# HP85disk.net
KiCad netlist of a schematic drawn in EAGLE
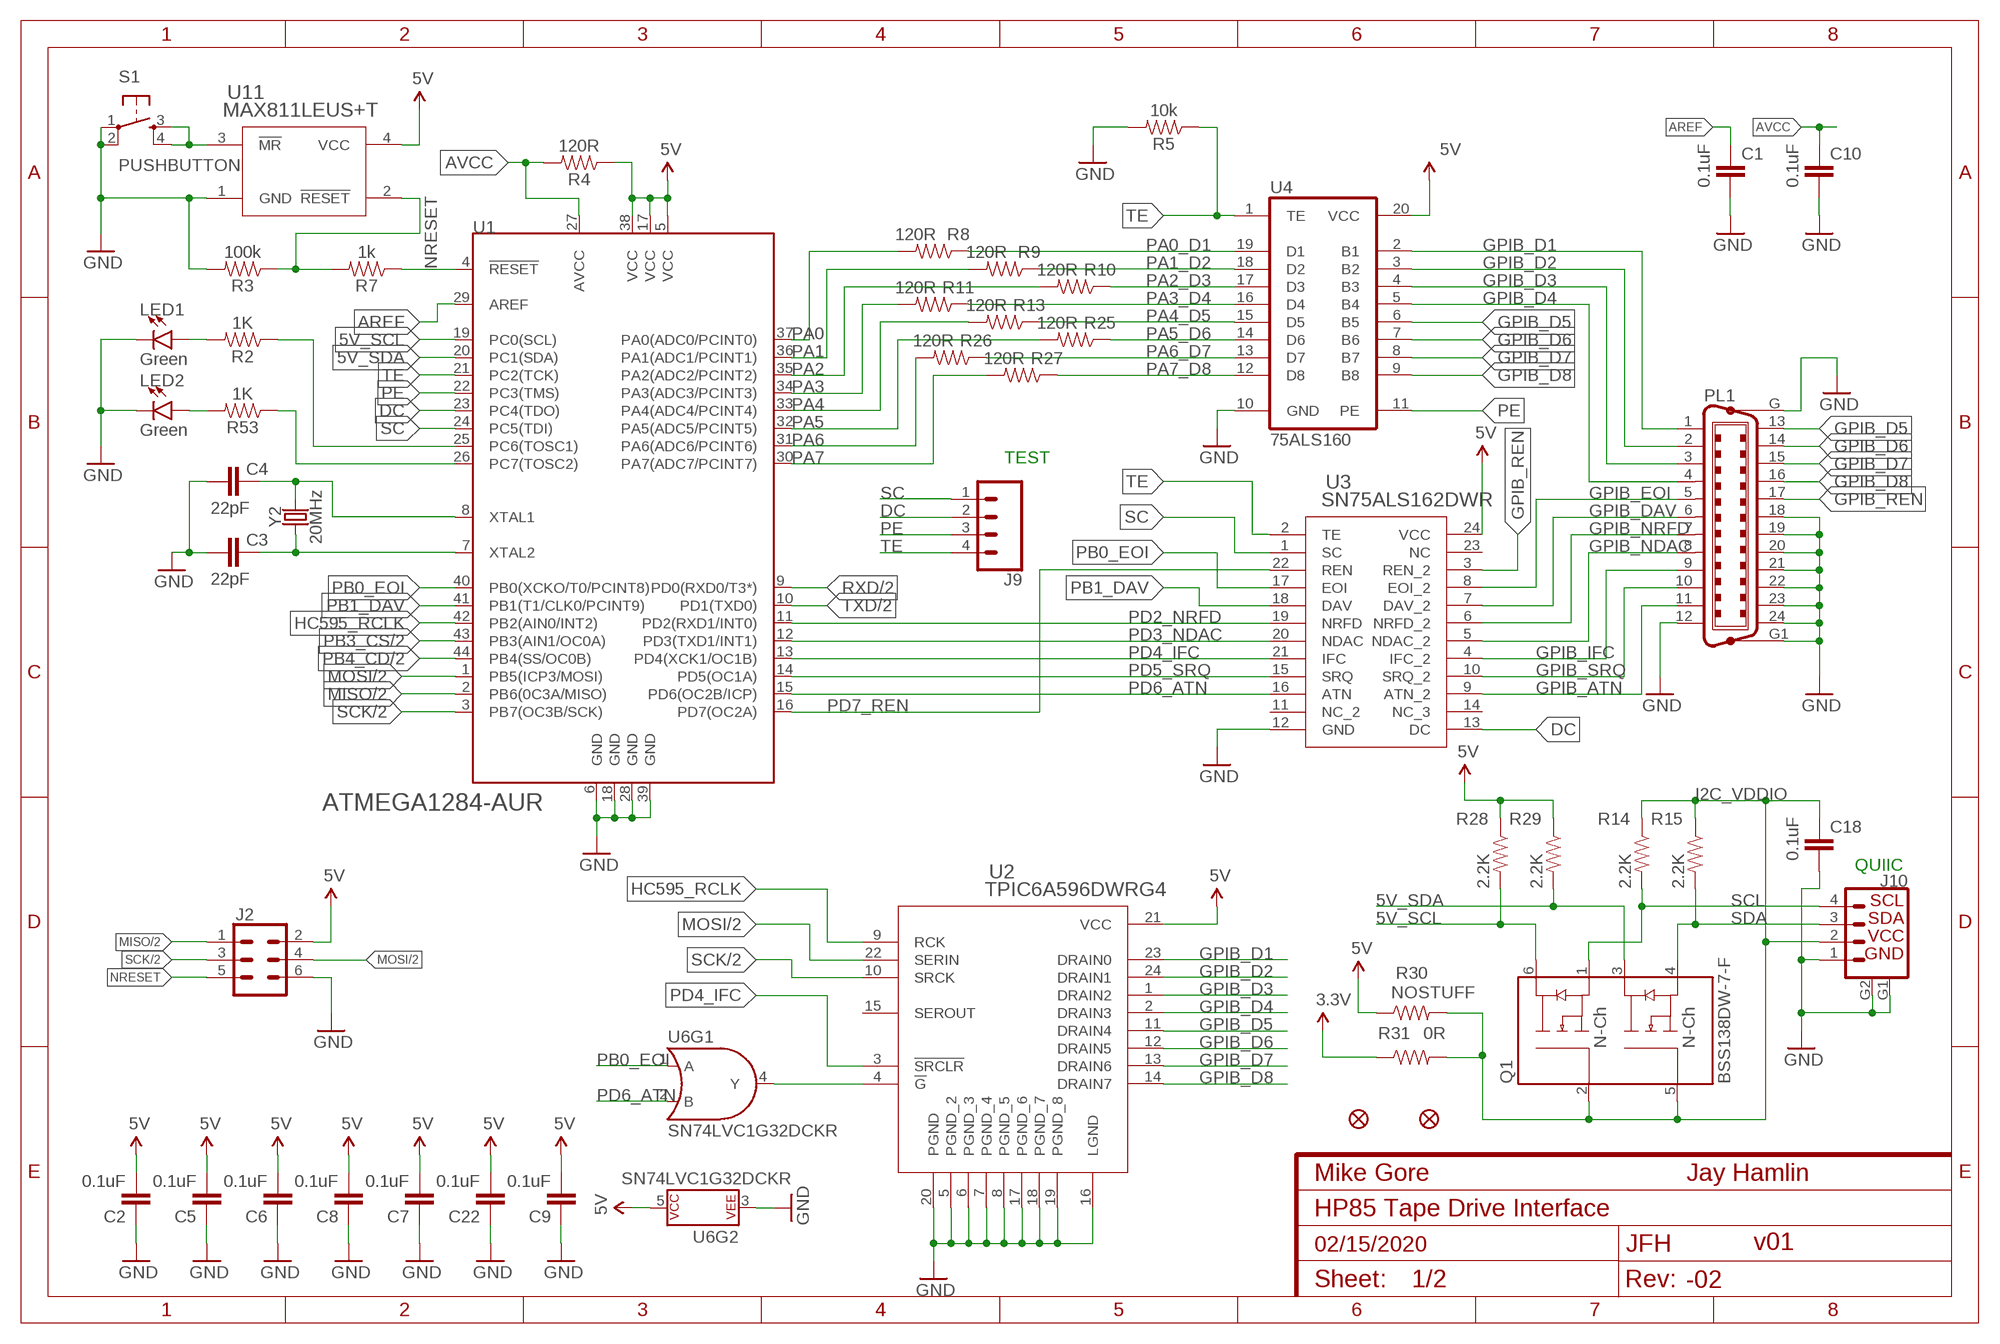
[diagram p0: schematic, sheet 1]
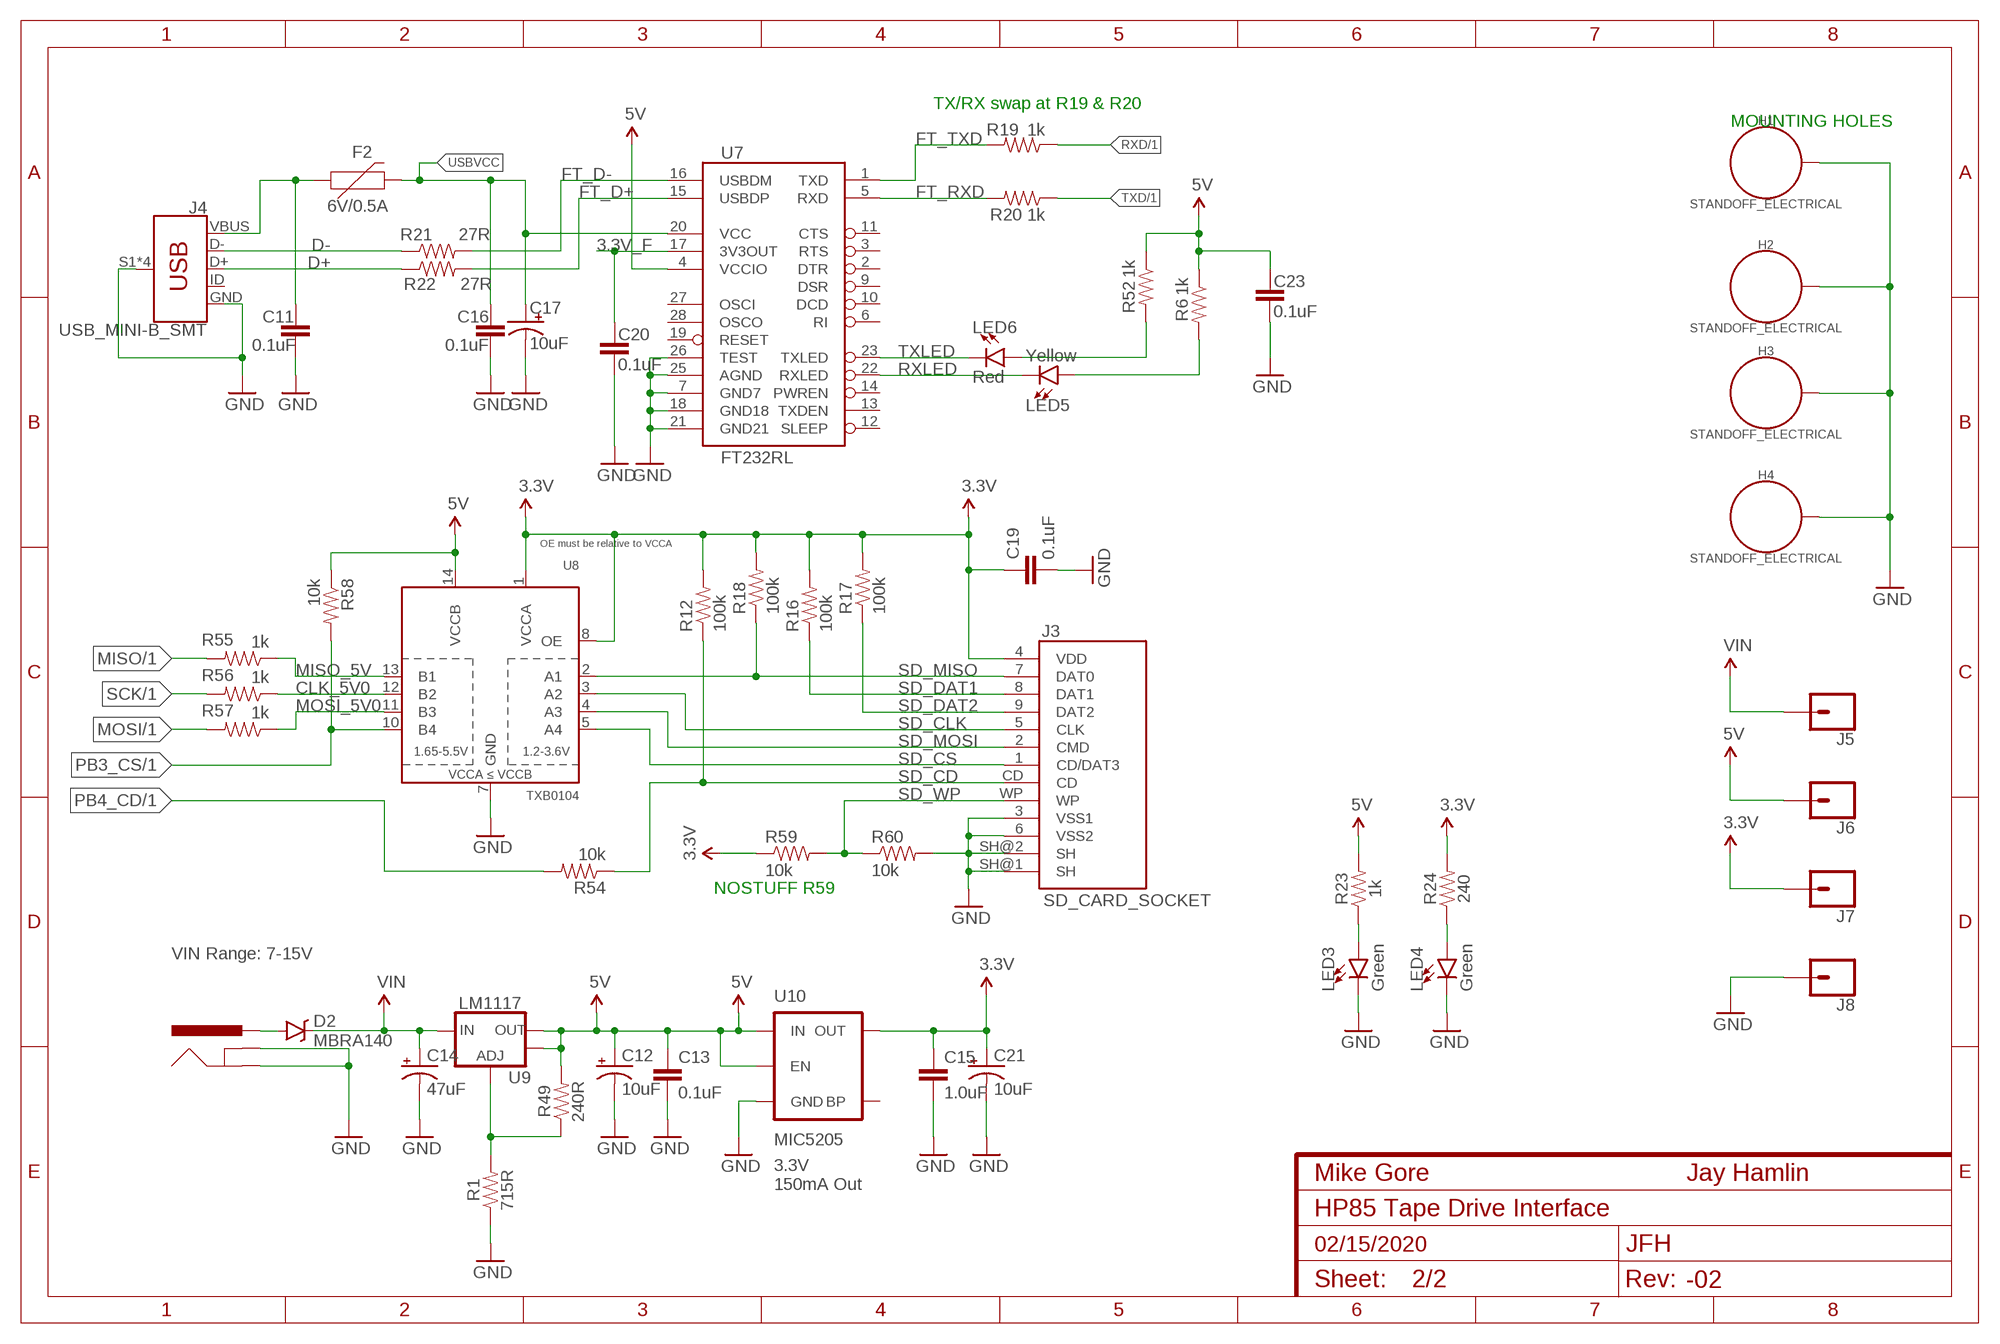
[diagram p1: schematic, sheet 2]

(export (version "E")
  (design (tool "Eeschema 10.0.6"))
  (components
    (comp (ref "C11")
      (value "0.1uF")
      (footprint "eagle-import:0603")
      (libsource (lib "eagle-import") (part "0.1UF-0603-25V-(+80/-20%)"))
    )
    (comp (ref "C12")
      (value "10uF")
      (footprint "eagle-import:EIA3216")
      (libsource (lib "eagle-import") (part "10UF-POLAR-EIA3216-16V-10%(TANT)"))
    )
    (comp (ref "C13")
      (value "0.1uF")
      (footprint "eagle-import:0603")
      (libsource (lib "eagle-import") (part "0.1UF-0603-25V-(+80/-20%)"))
    )
    (comp (ref "C14")
      (value "47uF")
      (footprint "eagle-import:PANASONIC_D")
      (libsource (lib "eagle-import") (part "47UF-POLAR-PANASONIC_D-35V-20%"))
    )
    (comp (ref "C15")
      (value "1.0uF")
      (footprint "eagle-import:0603")
      (libsource (lib "eagle-import") (part "1.0UF-0603-16V-10%"))
    )
    (comp (ref "C16")
      (value "0.1uF")
      (footprint "eagle-import:0603")
      (libsource (lib "eagle-import") (part "0.1UF-0603-25V-(+80/-20%)"))
    )
    (comp (ref "C17")
      (value "10uF")
      (footprint "eagle-import:EIA3216")
      (libsource (lib "eagle-import") (part "10UF-POLAR-EIA3216-16V-10%(TANT)"))
    )
    (comp (ref "C19")
      (value "0.1uF")
      (footprint "eagle-import:0603")
      (libsource (lib "eagle-import") (part "0.1UF-0603-25V-(+80/-20%)"))
    )
    (comp (ref "C20")
      (value "0.1uF")
      (footprint "eagle-import:0603")
      (libsource (lib "eagle-import") (part "0.1UF-0603-25V-(+80/-20%)"))
    )
    (comp (ref "C21")
      (value "10uF")
      (footprint "eagle-import:EIA3216")
      (libsource (lib "eagle-import") (part "10UF-POLAR-EIA3216-16V-10%(TANT)"))
    )
    (comp (ref "C23")
      (value "0.1uF")
      (footprint "eagle-import:0603")
      (libsource (lib "eagle-import") (part "0.1UF-0603-25V-(+80/-20%)"))
    )
    (comp (ref "D2")
      (value "MBRA140")
      (footprint "eagle-import:SMA-DIODE")
      (libsource (lib "eagle-import") (part "MBRA140"))
    )
    (comp (ref "F2")
      (value "6V/0.5A")
      (footprint "eagle-import:1206")
      (libsource (lib "eagle-import") (part "PTC-HALF_AMP"))
    )
    (comp (ref "H1")
      (value "STANDOFF_ELECTRICAL")
      (footprint "eagle-import:STANDOFF-ELECTRICAL")
      (libsource (lib "eagle-import") (part "STANDOFF_ELECTRICAL"))
    )
    (comp (ref "H2")
      (value "STANDOFF_ELECTRICAL")
      (footprint "eagle-import:STANDOFF-ELECTRICAL")
      (libsource (lib "eagle-import") (part "STANDOFF_ELECTRICAL"))
    )
    (comp (ref "H3")
      (value "STANDOFF_ELECTRICAL")
      (footprint "eagle-import:STANDOFF-ELECTRICAL")
      (libsource (lib "eagle-import") (part "STANDOFF_ELECTRICAL"))
    )
    (comp (ref "H4")
      (value "STANDOFF_ELECTRICAL")
      (footprint "eagle-import:STANDOFF-ELECTRICAL")
      (libsource (lib "eagle-import") (part "STANDOFF_ELECTRICAL"))
    )
    (comp (ref "J1")
      (value "POWER_JACKSUPER_BOMB_DIGITY")
      (footprint "eagle-import:POWER_JACK_SMD_OVERPASTE_SUPER_BOMB_DIGITY")
      (libsource (lib "eagle-import") (part "POWER_JACKSUPER_BOMB_DIGITY"))
    )
    (comp (ref "J3")
      (value "SD_CARD_SOCKET")
      (footprint "eagle-import:SD_1_1")
      (libsource (lib "eagle-import") (part "SD_CARD_SOCKET"))
    )
    (comp (ref "J4")
      (value "USB_MINI-B_SMT")
      (footprint "eagle-import:USB-MINIB")
      (libsource (lib "eagle-import") (part "USB_MINI-B_SMT"))
    )
    (comp (ref "J5")
      (value "CONN_01")
      (footprint "eagle-import:1X01")
      (libsource (lib "eagle-import") (part "CONN_01"))
    )
    (comp (ref "J6")
      (value "CONN_01")
      (footprint "eagle-import:1X01")
      (libsource (lib "eagle-import") (part "CONN_01"))
    )
    (comp (ref "J7")
      (value "CONN_01")
      (footprint "eagle-import:1X01")
      (libsource (lib "eagle-import") (part "CONN_01"))
    )
    (comp (ref "J8")
      (value "CONN_01")
      (footprint "eagle-import:1X01")
      (libsource (lib "eagle-import") (part "CONN_01"))
    )
    (comp (ref "LED3")
      (value "Green")
      (footprint "eagle-import:LED-1206")
      (libsource (lib "eagle-import") (part "LED1206"))
    )
    (comp (ref "LED4")
      (value "Green")
      (footprint "eagle-import:LED-1206")
      (libsource (lib "eagle-import") (part "LED1206"))
    )
    (comp (ref "LED5")
      (value "Yellow")
      (footprint "eagle-import:LED-1206")
      (libsource (lib "eagle-import") (part "LED1206"))
    )
    (comp (ref "LED6")
      (value "Red")
      (footprint "eagle-import:LED-1206")
      (libsource (lib "eagle-import") (part "LED1206"))
    )
    (comp (ref "R1")
      (value "715R")
      (footprint "eagle-import:0603")
      (libsource (lib "eagle-import") (part "715OHM-0603-1/10W-1%"))
    )
    (comp (ref "R6")
      (value "1k")
      (footprint "eagle-import:0603")
      (libsource (lib "eagle-import") (part "1KOHM-0603-1/10W-1%"))
    )
    (comp (ref "R12")
      (value "100k")
      (footprint "eagle-import:0603-RES")
      (libsource (lib "eagle-import") (part "100KOHM-1/10W-1%(0603)"))
    )
    (comp (ref "R16")
      (value "100k")
      (footprint "eagle-import:0603-RES")
      (libsource (lib "eagle-import") (part "100KOHM-1/10W-1%(0603)"))
    )
    (comp (ref "R17")
      (value "100k")
      (footprint "eagle-import:0603-RES")
      (libsource (lib "eagle-import") (part "100KOHM-1/10W-1%(0603)"))
    )
    (comp (ref "R18")
      (value "100k")
      (footprint "eagle-import:0603-RES")
      (libsource (lib "eagle-import") (part "100KOHM-1/10W-1%(0603)"))
    )
    (comp (ref "R19")
      (value "1k")
      (footprint "eagle-import:0603")
      (libsource (lib "eagle-import") (part "1KOHM-0603-1/10W-1%"))
    )
    (comp (ref "R20")
      (value "1k")
      (footprint "eagle-import:0603")
      (libsource (lib "eagle-import") (part "1KOHM-0603-1/10W-1%"))
    )
    (comp (ref "R21")
      (value "27R")
      (footprint "eagle-import:0603")
      (libsource (lib "eagle-import") (part "27OHM-0603-1/10W-1%"))
    )
    (comp (ref "R22")
      (value "27R")
      (footprint "eagle-import:0603")
      (libsource (lib "eagle-import") (part "27OHM-0603-1/10W-1%"))
    )
    (comp (ref "R23")
      (value "1k")
      (footprint "eagle-import:0603")
      (libsource (lib "eagle-import") (part "4.7KOHM-0603-1/10W-1%"))
    )
    (comp (ref "R24")
      (value "240")
      (footprint "eagle-import:0603")
      (libsource (lib "eagle-import") (part "4.7KOHM-0603-1/10W-1%"))
    )
    (comp (ref "R49")
      (value "240R")
      (footprint "eagle-import:0603")
      (libsource (lib "eagle-import") (part "240OHM-0603-1/10W-1%"))
    )
    (comp (ref "R52")
      (value "1k")
      (footprint "eagle-import:0603")
      (libsource (lib "eagle-import") (part "1KOHM-0603-1/10W-1%"))
    )
    (comp (ref "R54")
      (value "10k")
      (footprint "eagle-import:0603-RES")
      (libsource (lib "eagle-import") (part "100KOHM-1/10W-1%(0603)"))
    )
    (comp (ref "R55")
      (value "1k")
      (footprint "eagle-import:0603-RES")
      (libsource (lib "eagle-import") (part "100KOHM-1/10W-1%(0603)"))
    )
    (comp (ref "R56")
      (value "1k")
      (footprint "eagle-import:0603-RES")
      (libsource (lib "eagle-import") (part "100KOHM-1/10W-1%(0603)"))
    )
    (comp (ref "R57")
      (value "1k")
      (footprint "eagle-import:0603-RES")
      (libsource (lib "eagle-import") (part "100KOHM-1/10W-1%(0603)"))
    )
    (comp (ref "R58")
      (value "10k")
      (footprint "eagle-import:0603-RES")
      (libsource (lib "eagle-import") (part "100KOHM-1/10W-1%(0603)"))
    )
    (comp (ref "R59")
      (value "10k")
      (footprint "eagle-import:0603-RES")
      (libsource (lib "eagle-import") (part "100KOHM-1/10W-1%(0603)"))
    )
    (comp (ref "R60")
      (value "10k")
      (footprint "eagle-import:0603-RES")
      (libsource (lib "eagle-import") (part "100KOHM-1/10W-1%(0603)"))
    )
    (comp (ref "U7")
      (value "FT232RL")
      (footprint "eagle-import:SSOP28DB")
      (libsource (lib "eagle-import") (part "FT232RLSSOP"))
    )
    (comp (ref "U8")
      (value "TXB0104")
      (footprint "eagle-import:SO14")
      (libsource (lib "eagle-import") (part "TXB0104PWRSOIC14"))
    )
    (comp (ref "U9")
      (value "LM1117")
      (footprint "eagle-import:SOT223-ALT1")
      (libsource (lib "eagle-import") (part "V_REG_LM1117ALT1"))
    )
    (comp (ref "U10")
      (value "MIC5205")
      (footprint "eagle-import:SOT23-5")
      (libsource (lib "eagle-import") (part "MIC52053.3V"))
    )
    (comp (ref "C1")
      (value "0.1uF")
      (footprint "eagle-import:0603")
      (libsource (lib "eagle-import") (part "0.1UF-0603-25V-(+80/-20%)"))
    )
    (comp (ref "C2")
      (value "0.1uF")
      (footprint "eagle-import:0603")
      (fields (field (name "SPICEPREFIX") "C"))
      (libsource (lib "eagle-import") (part "0.1UF-0603-25V-(+80/-20%)"))
    )
    (comp (ref "C3")
      (value "22pF")
      (footprint "eagle-import:0603")
      (libsource (lib "eagle-import") (part "0.1UF-0603-25V-(+80/-20%)"))
    )
    (comp (ref "C4")
      (value "22pF")
      (footprint "eagle-import:0603")
      (libsource (lib "eagle-import") (part "0.1UF-0603-25V-(+80/-20%)"))
    )
    (comp (ref "C5")
      (value "0.1uF")
      (footprint "eagle-import:0603")
      (fields (field (name "SPICEPREFIX") "C"))
      (libsource (lib "eagle-import") (part "0.1UF-0603-25V-(+80/-20%)"))
    )
    (comp (ref "C6")
      (value "0.1uF")
      (footprint "eagle-import:0603")
      (fields (field (name "SPICEPREFIX") "C"))
      (libsource (lib "eagle-import") (part "0.1UF-0603-25V-(+80/-20%)"))
    )
    (comp (ref "C7")
      (value "0.1uF")
      (footprint "eagle-import:0603")
      (fields (field (name "SPICEPREFIX") "C"))
      (libsource (lib "eagle-import") (part "0.1UF-0603-25V-(+80/-20%)"))
    )
    (comp (ref "C8")
      (value "0.1uF")
      (footprint "eagle-import:0603")
      (fields (field (name "SPICEPREFIX") "C"))
      (libsource (lib "eagle-import") (part "0.1UF-0603-25V-(+80/-20%)"))
    )
    (comp (ref "C9")
      (value "0.1uF")
      (footprint "eagle-import:0603")
      (libsource (lib "eagle-import") (part "0.1UF-0603-25V-(+80/-20%)"))
    )
    (comp (ref "C10")
      (value "0.1uF")
      (footprint "eagle-import:0603")
      (libsource (lib "eagle-import") (part "0.1UF-0603-25V-(+80/-20%)"))
    )
    (comp (ref "C18")
      (value "0.1uF")
      (footprint "eagle-import:0603")
      (libsource (lib "eagle-import") (part "0.1UF-0603-25V-(+80/-20%)"))
    )
    (comp (ref "C22")
      (value "0.1uF")
      (footprint "eagle-import:0603")
      (libsource (lib "eagle-import") (part "0.1UF-0603-25V-(+80/-20%)"))
    )
    (comp (ref "J2")
      (value "CONN_03X2_BIGPADSFEMALE_SMD")
      (footprint "eagle-import:2X3_SMD")
      (libsource (lib "eagle-import") (part "CONN_03X2_BIGPADSFEMALE_SMD"))
    )
    (comp (ref "J9")
      (value "CONN_041.27MM")
      (footprint "eagle-import:1X04_1.27MM")
      (libsource (lib "eagle-import") (part "CONN_041.27MM"))
    )
    (comp (ref "J10")
      (value "QWIIC_CONNECTORJS-1MM")
      (footprint "eagle-import:QUIIC_1X04_1MM_RA")
      (libsource (lib "eagle-import") (part "QWIIC_CONNECTORJS-1MM"))
    )
    (comp (ref "JP8")
      (value "FIDUCIAL1X2")
      (footprint "eagle-import:FIDUCIAL-1X2")
      (libsource (lib "eagle-import") (part "FIDUCIAL1X2"))
    )
    (comp (ref "JP9")
      (value "FIDUCIAL1X2")
      (footprint "eagle-import:FIDUCIAL-1X2")
      (libsource (lib "eagle-import") (part "FIDUCIAL1X2"))
    )
    (comp (ref "LED1")
      (value "Green")
      (footprint "eagle-import:LED-1206")
      (libsource (lib "eagle-import") (part "LED1206"))
    )
    (comp (ref "LED2")
      (value "Green")
      (footprint "eagle-import:LED-1206")
      (libsource (lib "eagle-import") (part "LED1206"))
    )
    (comp (ref "PL1")
      (value "C24HP")
      (footprint "eagle-import:24HP")
      (libsource (lib "eagle-import") (part "C24HP"))
    )
    (comp (ref "Q1")
      (value "BSS138DW-7-F")
      (footprint "eagle-import:SOT-363")
      (libsource (lib "eagle-import") (part "BSS138DW-7-F"))
    )
    (comp (ref "R2")
      (value "1K")
      (footprint "eagle-import:0603")
      (libsource (lib "eagle-import") (part "4.7KOHM-0603-1/10W-1%"))
    )
    (comp (ref "R3")
      (value "100k")
      (footprint "eagle-import:0603")
      (libsource (lib "eagle-import") (part "10KOHM-0603-1/10W-1%"))
    )
    (comp (ref "R4")
      (value "120R")
      (footprint "eagle-import:0603")
      (libsource (lib "eagle-import") (part "10KOHM-0603-1/10W-1%"))
    )
    (comp (ref "R5")
      (value "10k")
      (footprint "eagle-import:0603")
      (libsource (lib "eagle-import") (part "10KOHM-0603-1/10W-1%"))
    )
    (comp (ref "R7")
      (value "1k")
      (footprint "eagle-import:0603")
      (libsource (lib "eagle-import") (part "10KOHM-0603-1/10W-1%"))
    )
    (comp (ref "R8")
      (value "120R")
      (footprint "eagle-import:0603")
      (libsource (lib "eagle-import") (part "10KOHM-0603-1/10W-1%"))
    )
    (comp (ref "R9")
      (value "120R")
      (footprint "eagle-import:0603")
      (libsource (lib "eagle-import") (part "10KOHM-0603-1/10W-1%"))
    )
    (comp (ref "R10")
      (value "120R")
      (footprint "eagle-import:0603")
      (libsource (lib "eagle-import") (part "10KOHM-0603-1/10W-1%"))
    )
    (comp (ref "R11")
      (value "120R")
      (footprint "eagle-import:0603")
      (libsource (lib "eagle-import") (part "10KOHM-0603-1/10W-1%"))
    )
    (comp (ref "R13")
      (value "120R")
      (footprint "eagle-import:0603")
      (libsource (lib "eagle-import") (part "10KOHM-0603-1/10W-1%"))
    )
    (comp (ref "R14")
      (value "2.2K")
      (footprint "eagle-import:0603")
      (libsource (lib "eagle-import") (part "10KOHM-0603-1/10W-1%"))
    )
    (comp (ref "R15")
      (value "2.2K")
      (footprint "eagle-import:0603")
      (libsource (lib "eagle-import") (part "10KOHM-0603-1/10W-1%"))
    )
    (comp (ref "R25")
      (value "120R")
      (footprint "eagle-import:0603")
      (libsource (lib "eagle-import") (part "10KOHM-0603-1/10W-1%"))
    )
    (comp (ref "R26")
      (value "120R")
      (footprint "eagle-import:0603")
      (libsource (lib "eagle-import") (part "10KOHM-0603-1/10W-1%"))
    )
    (comp (ref "R27")
      (value "120R")
      (footprint "eagle-import:0603")
      (libsource (lib "eagle-import") (part "10KOHM-0603-1/10W-1%"))
    )
    (comp (ref "R28")
      (value "2.2K")
      (footprint "eagle-import:0603")
      (libsource (lib "eagle-import") (part "10KOHM-0603-1/10W-1%"))
    )
    (comp (ref "R29")
      (value "2.2K")
      (footprint "eagle-import:0603")
      (libsource (lib "eagle-import") (part "10KOHM-0603-1/10W-1%"))
    )
    (comp (ref "R30")
      (value "NOSTUFF")
      (footprint "eagle-import:0603")
      (libsource (lib "eagle-import") (part "10KOHM-0603-1/10W-1%"))
    )
    (comp (ref "R31")
      (value "0R")
      (footprint "eagle-import:0603")
      (libsource (lib "eagle-import") (part "10KOHM-0603-1/10W-1%"))
    )
    (comp (ref "R53")
      (value "1K")
      (footprint "eagle-import:0603")
      (libsource (lib "eagle-import") (part "4.7KOHM-0603-1/10W-1%"))
    )
    (comp (ref "S1")
      (value "PUSHBUTTON")
      (footprint "eagle-import:TACTILE-SWITCH-SMD")
      (libsource (lib "eagle-import") (part "SWITCH_SPST_4_PINSQUARE"))
    )
    (comp (ref "U1")
      (value "ATMEGA1284-AUR")
      (footprint "eagle-import:TQFP44")
      (libsource (lib "eagle-import") (part "ATMEGA1284AUTQFP-44"))
    )
    (comp (ref "U2")
      (value "TPIC6A596DWRG4")
      (footprint "eagle-import:DW24")
      (fields (field (name "MANUFACTURER") "Texas Instruments"))
      (libsource (lib "eagle-import") (part "TPIC6A596DWRG4"))
    )
    (comp (ref "U3")
      (value "SN75ALS162DWR")
      (footprint "eagle-import:DW24")
      (fields (field (name "MANUFACTURER") "Texas Instruments"))
      (libsource (lib "eagle-import") (part "SN75ALS162DWR"))
    )
    (comp (ref "U4")
      (value "75ALS160")
      (footprint "eagle-import:SO20L")
      (libsource (lib "eagle-import") (part "75160SO"))
    )
    (comp (ref "U6")
      (value "SN74LVC1G32DCKR")
      (footprint "eagle-import:SOT23-5")
      (libsource (lib "eagle-import") (part "7432DBVLVC"))
    )
    (comp (ref "U11")
      (value "MAX811LEUS+T")
      (footprint "eagle-import:21-0052F")
      (fields
        (field (name "MANUFACTURER_PART_NUMBER") "MAX811TEUS+T")
        (field (name "COPYRIGHT") "Copyright (C) 2018 Accelerated Designs. All rights reserved")
      )
      (libsource (lib "eagle-import") (part "MAX811TEUS+T"))
    )
    (comp (ref "Y2")
      (value "20MHz")
      (footprint "eagle-import:CRYSTAL-SMD-5X3.2-4PAD")
      (libsource (lib "eagle-import") (part "CRYSTAL-16MHZSMD-5X3.2"))
    )
  )
  (nets
    (net (code "1") (name "3.3V") (class "Default")
      (node (ref "C15") (pin "1") (pinfunction "1_1") (pintype "passive"))
      (node (ref "C19") (pin "1") (pinfunction "1_1") (pintype "passive"))
      (node (ref "C21") (pin "+") (pinfunction "+_+") (pintype "passive"))
      (node (ref "J3") (pin "4") (pinfunction "VDD_4") (pintype "power_in"))
      (node (ref "J7") (pin "1") (pinfunction "1_1") (pintype "passive"))
      (node (ref "R12") (pin "2") (pinfunction "2_2") (pintype "passive"))
      (node (ref "R16") (pin "2") (pinfunction "2_2") (pintype "passive"))
      (node (ref "R17") (pin "2") (pinfunction "2_2") (pintype "passive"))
      (node (ref "R18") (pin "2") (pinfunction "2_2") (pintype "passive"))
      (node (ref "R24") (pin "2") (pinfunction "2_2") (pintype "passive"))
      (node (ref "R31") (pin "1") (pinfunction "1_1") (pintype "passive"))
      (node (ref "R59") (pin "1") (pinfunction "1_1") (pintype "passive"))
      (node (ref "U10") (pin "5") (pinfunction "OUT_5") (pintype "passive"))
      (node (ref "U8") (pin "1") (pinfunction "VCCA_1") (pintype "bidirectional"))
      (node (ref "U8") (pin "8") (pinfunction "OE_8") (pintype "bidirectional"))
    )
    (net (code "2") (name "3.3V_F") (class "Default")
      (node (ref "C20") (pin "1") (pinfunction "1_1") (pintype "passive"))
      (node (ref "U7") (pin "17") (pinfunction "3V3OUT_17") (pintype "output"))
    )
    (net (code "3") (name "5V") (class "Default")
      (node (ref "C12") (pin "+") (pinfunction "+_+") (pintype "passive"))
      (node (ref "C13") (pin "1") (pinfunction "1_1") (pintype "passive"))
      (node (ref "C2") (pin "2") (pinfunction "2_2") (pintype "passive"))
      (node (ref "C22") (pin "2") (pinfunction "2_2") (pintype "passive"))
      (node (ref "C23") (pin "1") (pinfunction "1_1") (pintype "passive"))
      (node (ref "C5") (pin "2") (pinfunction "2_2") (pintype "passive"))
      (node (ref "C6") (pin "2") (pinfunction "2_2") (pintype "passive"))
      (node (ref "C7") (pin "2") (pinfunction "2_2") (pintype "passive"))
      (node (ref "C8") (pin "2") (pinfunction "2_2") (pintype "passive"))
      (node (ref "C9") (pin "2") (pinfunction "2_2") (pintype "passive"))
      (node (ref "J2") (pin "2") (pinfunction "2_2") (pintype "bidirectional"))
      (node (ref "J6") (pin "1") (pinfunction "1_1") (pintype "passive"))
      (node (ref "R23") (pin "2") (pinfunction "2_2") (pintype "passive"))
      (node (ref "R28") (pin "1") (pinfunction "1_1") (pintype "passive"))
      (node (ref "R29") (pin "1") (pinfunction "1_1") (pintype "passive"))
      (node (ref "R30") (pin "1") (pinfunction "1_1") (pintype "passive"))
      (node (ref "R4") (pin "1") (pinfunction "1_1") (pintype "passive"))
      (node (ref "R49") (pin "2") (pinfunction "2_2") (pintype "passive"))
      (node (ref "R52") (pin "1") (pinfunction "1_1") (pintype "passive"))
      (node (ref "R58") (pin "1") (pinfunction "1_1") (pintype "passive"))
      (node (ref "R6") (pin "1") (pinfunction "1_1") (pintype "passive"))
      (node (ref "U1") (pin "17") (pinfunction "VCC_17") (pintype "bidirectional"))
      (node (ref "U1") (pin "38") (pinfunction "VCC_38") (pintype "bidirectional"))
      (node (ref "U1") (pin "5") (pinfunction "VCC_5") (pintype "bidirectional"))
      (node (ref "U10") (pin "1") (pinfunction "IN_1") (pintype "input"))
      (node (ref "U10") (pin "3") (pinfunction "EN_3") (pintype "input"))
      (node (ref "U11") (pin "4") (pinfunction "VCC_4") (pintype "power_in"))
      (node (ref "U2") (pin "21") (pinfunction "VCC_21") (pintype "power_in"))
      (node (ref "U3") (pin "24") (pinfunction "VCC_24") (pintype "power_in"))
      (node (ref "U4") (pin "20") (pinfunction "VCC_20") (pintype "bidirectional"))
      (node (ref "U6") (pin "5") (pinfunction "P$V+_5") (pintype "bidirectional"))
      (node (ref "U7") (pin "4") (pinfunction "VCCIO_4") (pintype "power_in"))
      (node (ref "U8") (pin "14") (pinfunction "VCCB_14") (pintype "bidirectional"))
      (node (ref "U9") (pin "2") (pinfunction "OUT_2") (pintype "output"))
      (node (ref "U9") (pin "4") (pinfunction "OUT_4") (pintype "output"))
    )
    (net (code "4") (name "5V_SCL") (class "Default")
      (node (ref "Q1") (pin "6") (pinfunction "D1_6") (pintype "bidirectional"))
      (node (ref "R28") (pin "2") (pinfunction "2_2") (pintype "passive"))
      (node (ref "U1") (pin "19") (pinfunction "PC0(SCL)_19") (pintype "bidirectional"))
    )
    (net (code "5") (name "5V_SDA") (class "Default")
      (node (ref "Q1") (pin "3") (pinfunction "D2_3") (pintype "bidirectional"))
      (node (ref "R29") (pin "2") (pinfunction "2_2") (pintype "passive"))
      (node (ref "U1") (pin "20") (pinfunction "PC1(SDA)_20") (pintype "bidirectional"))
    )
    (net (code "6") (name "AREF") (class "Default")
      (node (ref "C1") (pin "1") (pinfunction "1_1") (pintype "passive"))
      (node (ref "U1") (pin "29") (pinfunction "AREF_29") (pintype "bidirectional"))
    )
    (net (code "7") (name "AVCC") (class "Default")
      (node (ref "C10") (pin "1") (pinfunction "1_1") (pintype "passive"))
      (node (ref "R4") (pin "2") (pinfunction "2_2") (pintype "passive"))
      (node (ref "U1") (pin "27") (pinfunction "AVCC_27") (pintype "bidirectional"))
    )
    (net (code "8") (name "CLK_5V0") (class "Default")
      (node (ref "R56") (pin "1") (pinfunction "1_1") (pintype "passive"))
      (node (ref "U8") (pin "12") (pinfunction "B2_12") (pintype "bidirectional"))
    )
    (net (code "9") (name "D+") (class "Default")
      (node (ref "J4") (pin "D+") (pinfunction "D+_D+") (pintype "bidirectional"))
      (node (ref "R22") (pin "1") (pinfunction "1_1") (pintype "passive"))
    )
    (net (code "10") (name "D-") (class "Default")
      (node (ref "J4") (pin "D-") (pinfunction "D-_D-") (pintype "bidirectional"))
      (node (ref "R21") (pin "1") (pinfunction "1_1") (pintype "passive"))
    )
    (net (code "11") (name "DC") (class "Default")
      (node (ref "J9") (pin "2") (pinfunction "2_2") (pintype "passive"))
      (node (ref "U1") (pin "23") (pinfunction "PC4(TDO)_23") (pintype "bidirectional"))
      (node (ref "U3") (pin "13") (pinfunction "DC_13") (pintype "input"))
    )
    (net (code "12") (name "FT_D+") (class "Default")
      (node (ref "R22") (pin "2") (pinfunction "2_2") (pintype "passive"))
      (node (ref "U7") (pin "15") (pinfunction "USBDP_15") (pintype "bidirectional"))
    )
    (net (code "13") (name "FT_D-") (class "Default")
      (node (ref "R21") (pin "2") (pinfunction "2_2") (pintype "passive"))
      (node (ref "U7") (pin "16") (pinfunction "USBDM_16") (pintype "bidirectional"))
    )
    (net (code "14") (name "FT_RXD") (class "Default")
      (node (ref "R20") (pin "2") (pinfunction "2_2") (pintype "passive"))
      (node (ref "U7") (pin "5") (pinfunction "RXD_5") (pintype "input"))
    )
    (net (code "15") (name "FT_TXD") (class "Default")
      (node (ref "R19") (pin "2") (pinfunction "2_2") (pintype "passive"))
      (node (ref "U7") (pin "1") (pinfunction "TXD_1") (pintype "output"))
    )
    (net (code "16") (name "GND") (class "Default")
      (node (ref "C1") (pin "2") (pinfunction "2_2") (pintype "passive"))
      (node (ref "C10") (pin "2") (pinfunction "2_2") (pintype "passive"))
      (node (ref "C11") (pin "2") (pinfunction "2_2") (pintype "passive"))
      (node (ref "C12") (pin "-") (pinfunction "-_-") (pintype "passive"))
      (node (ref "C13") (pin "2") (pinfunction "2_2") (pintype "passive"))
      (node (ref "C14") (pin "-") (pinfunction "-_-") (pintype "passive"))
      (node (ref "C15") (pin "2") (pinfunction "2_2") (pintype "passive"))
      (node (ref "C16") (pin "2") (pinfunction "2_2") (pintype "passive"))
      (node (ref "C17") (pin "-") (pinfunction "-_-") (pintype "passive"))
      (node (ref "C18") (pin "2") (pinfunction "2_2") (pintype "passive"))
      (node (ref "C19") (pin "2") (pinfunction "2_2") (pintype "passive"))
      (node (ref "C2") (pin "1") (pinfunction "1_1") (pintype "passive"))
      (node (ref "C20") (pin "2") (pinfunction "2_2") (pintype "passive"))
      (node (ref "C21") (pin "-") (pinfunction "-_-") (pintype "passive"))
      (node (ref "C22") (pin "1") (pinfunction "1_1") (pintype "passive"))
      (node (ref "C23") (pin "2") (pinfunction "2_2") (pintype "passive"))
      (node (ref "C3") (pin "1") (pinfunction "1_1") (pintype "passive"))
      (node (ref "C4") (pin "1") (pinfunction "1_1") (pintype "passive"))
      (node (ref "C5") (pin "1") (pinfunction "1_1") (pintype "passive"))
      (node (ref "C6") (pin "1") (pinfunction "1_1") (pintype "passive"))
      (node (ref "C7") (pin "1") (pinfunction "1_1") (pintype "passive"))
      (node (ref "C8") (pin "1") (pinfunction "1_1") (pintype "passive"))
      (node (ref "C9") (pin "1") (pinfunction "1_1") (pintype "passive"))
      (node (ref "H1") (pin "P1") (pinfunction "P$1_P1") (pintype "bidirectional"))
      (node (ref "H2") (pin "P1") (pinfunction "P$1_P1") (pintype "bidirectional"))
      (node (ref "H3") (pin "P1") (pinfunction "P$1_P1") (pintype "bidirectional"))
      (node (ref "H4") (pin "P1") (pinfunction "P$1_P1") (pintype "bidirectional"))
      (node (ref "J1") (pin "GND") (pinfunction "GNDBREAK_GND") (pintype "bidirectional"))
      (node (ref "J1") (pin "P$4") (pinfunction "GND_P$4") (pintype "bidirectional"))
      (node (ref "J10") (pin "1") (pinfunction "1_1") (pintype "power_in"))
      (node (ref "J10") (pin "G1") (pinfunction "G1_G1") (pintype "power_in"))
      (node (ref "J10") (pin "G2") (pinfunction "G2_G2") (pintype "power_in"))
      (node (ref "J2") (pin "6") (pinfunction "6_6") (pintype "bidirectional"))
      (node (ref "J3") (pin "3") (pinfunction "VSS1_3") (pintype "power_in"))
      (node (ref "J3") (pin "6") (pinfunction "VSS2_6") (pintype "power_in"))
      (node (ref "J3") (pin "SH@1") (pinfunction "SH_SH@1") (pintype "bidirectional"))
      (node (ref "J3") (pin "SH@2") (pinfunction "SH_SH@2") (pintype "bidirectional"))
      (node (ref "J4") (pin "GND") (pinfunction "GND_GND") (pintype "power_in"))
      (node (ref "J4") (pin "S1") (pinfunction "SHIELD_S1") (pintype "bidirectional"))
      (node (ref "J4") (pin "S2") (pinfunction "SHIELD_S2") (pintype "bidirectional"))
      (node (ref "J4") (pin "S3") (pinfunction "SHIELD_S3") (pintype "bidirectional"))
      (node (ref "J4") (pin "S4") (pinfunction "SHIELD_S4") (pintype "bidirectional"))
      (node (ref "J8") (pin "1") (pinfunction "1_1") (pintype "passive"))
      (node (ref "LED1") (pin "C") (pinfunction "C_C") (pintype "passive"))
      (node (ref "LED2") (pin "C") (pinfunction "C_C") (pintype "passive"))
      (node (ref "LED3") (pin "C") (pinfunction "C_C") (pintype "passive"))
      (node (ref "LED4") (pin "C") (pinfunction "C_C") (pintype "passive"))
      (node (ref "PL1") (pin "12") (pinfunction "12_12") (pintype "passive"))
      (node (ref "PL1") (pin "18") (pinfunction "18_18") (pintype "passive"))
      (node (ref "PL1") (pin "19") (pinfunction "19_19") (pintype "passive"))
      (node (ref "PL1") (pin "20") (pinfunction "20_20") (pintype "passive"))
      (node (ref "PL1") (pin "21") (pinfunction "21_21") (pintype "passive"))
      (node (ref "PL1") (pin "22") (pinfunction "22_22") (pintype "passive"))
      (node (ref "PL1") (pin "23") (pinfunction "23_23") (pintype "passive"))
      (node (ref "PL1") (pin "24") (pinfunction "24_24") (pintype "passive"))
      (node (ref "PL1") (pin "G") (pinfunction "G_G") (pintype "passive"))
      (node (ref "PL1") (pin "G1") (pinfunction "G1_G1") (pintype "passive"))
      (node (ref "R1") (pin "1") (pinfunction "1_1") (pintype "passive"))
      (node (ref "R3") (pin "2") (pinfunction "2_2") (pintype "passive"))
      (node (ref "R5") (pin "2") (pinfunction "2_2") (pintype "passive"))
      (node (ref "R60") (pin "2") (pinfunction "2_2") (pintype "passive"))
      (node (ref "S1") (pin "1") (pinfunction "1_1") (pintype "passive"))
      (node (ref "S1") (pin "2") (pinfunction "2_2") (pintype "passive"))
      (node (ref "U1") (pin "18") (pinfunction "GND_18") (pintype "bidirectional"))
      (node (ref "U1") (pin "28") (pinfunction "GND_28") (pintype "bidirectional"))
      (node (ref "U1") (pin "39") (pinfunction "GND_39") (pintype "bidirectional"))
      (node (ref "U1") (pin "6") (pinfunction "GND_6") (pintype "bidirectional"))
      (node (ref "U10") (pin "2") (pinfunction "GND_2") (pintype "input"))
      (node (ref "U11") (pin "1") (pinfunction "GND_1") (pintype "power_in"))
      (node (ref "U2") (pin "16") (pinfunction "LGND_16") (pintype "power_in"))
      (node (ref "U2") (pin "17") (pinfunction "PGND_6_17") (pintype "power_in"))
      (node (ref "U2") (pin "18") (pinfunction "PGND_7_18") (pintype "power_in"))
      (node (ref "U2") (pin "19") (pinfunction "PGND_8_19") (pintype "power_in"))
      (node (ref "U2") (pin "20") (pinfunction "PGND_20") (pintype "power_in"))
      (node (ref "U2") (pin "5") (pinfunction "PGND_2_5") (pintype "power_in"))
      (node (ref "U2") (pin "6") (pinfunction "PGND_3_6") (pintype "power_in"))
      (node (ref "U2") (pin "7") (pinfunction "PGND_4_7") (pintype "power_in"))
      (node (ref "U2") (pin "8") (pinfunction "PGND_5_8") (pintype "power_in"))
      (node (ref "U3") (pin "12") (pinfunction "GND_12") (pintype "power_in"))
      (node (ref "U4") (pin "10") (pinfunction "GND_10") (pintype "bidirectional"))
      (node (ref "U6") (pin "3") (pinfunction "P$V-_3") (pintype "bidirectional"))
      (node (ref "U7") (pin "18") (pinfunction "GND18_18") (pintype "power_in"))
      (node (ref "U7") (pin "21") (pinfunction "GND21_21") (pintype "power_in"))
      (node (ref "U7") (pin "25") (pinfunction "AGND_25") (pintype "power_in"))
      (node (ref "U7") (pin "26") (pinfunction "TEST_26") (pintype "input"))
      (node (ref "U7") (pin "7") (pinfunction "GND7_7") (pintype "power_in"))
      (node (ref "U8") (pin "7") (pinfunction "GND_7") (pintype "bidirectional"))
    )
    (net (code "17") (name "GPIB_ATN") (class "Default")
      (node (ref "PL1") (pin "11") (pinfunction "11_11") (pintype "passive"))
      (node (ref "U3") (pin "9") (pinfunction "ATN_2_9") (pintype "bidirectional"))
    )
    (net (code "18") (name "GPIB_D1") (class "Default")
      (node (ref "PL1") (pin "1") (pinfunction "1_1") (pintype "passive"))
      (node (ref "U2") (pin "23") (pinfunction "DRAIN0_23") (pintype "output"))
      (node (ref "U4") (pin "2") (pinfunction "B1_2") (pintype "bidirectional"))
    )
    (net (code "19") (name "GPIB_D2") (class "Default")
      (node (ref "PL1") (pin "2") (pinfunction "2_2") (pintype "passive"))
      (node (ref "U2") (pin "24") (pinfunction "DRAIN1_24") (pintype "output"))
      (node (ref "U4") (pin "3") (pinfunction "B2_3") (pintype "bidirectional"))
    )
    (net (code "20") (name "GPIB_D3") (class "Default")
      (node (ref "PL1") (pin "3") (pinfunction "3_3") (pintype "passive"))
      (node (ref "U2") (pin "1") (pinfunction "DRAIN2_1") (pintype "output"))
      (node (ref "U4") (pin "4") (pinfunction "B3_4") (pintype "bidirectional"))
    )
    (net (code "21") (name "GPIB_D4") (class "Default")
      (node (ref "PL1") (pin "4") (pinfunction "4_4") (pintype "passive"))
      (node (ref "U2") (pin "2") (pinfunction "DRAIN3_2") (pintype "output"))
      (node (ref "U4") (pin "5") (pinfunction "B4_5") (pintype "bidirectional"))
    )
    (net (code "22") (name "GPIB_D5") (class "Default")
      (node (ref "PL1") (pin "13") (pinfunction "13_13") (pintype "passive"))
      (node (ref "U2") (pin "11") (pinfunction "DRAIN4_11") (pintype "output"))
      (node (ref "U4") (pin "6") (pinfunction "B5_6") (pintype "bidirectional"))
    )
    (net (code "23") (name "GPIB_D6") (class "Default")
      (node (ref "PL1") (pin "14") (pinfunction "14_14") (pintype "passive"))
      (node (ref "U2") (pin "12") (pinfunction "DRAIN5_12") (pintype "output"))
      (node (ref "U4") (pin "7") (pinfunction "B6_7") (pintype "bidirectional"))
    )
    (net (code "24") (name "GPIB_D7") (class "Default")
      (node (ref "PL1") (pin "15") (pinfunction "15_15") (pintype "passive"))
      (node (ref "U2") (pin "13") (pinfunction "DRAIN6_13") (pintype "output"))
      (node (ref "U4") (pin "8") (pinfunction "B7_8") (pintype "bidirectional"))
    )
    (net (code "25") (name "GPIB_D8") (class "Default")
      (node (ref "PL1") (pin "16") (pinfunction "16_16") (pintype "passive"))
      (node (ref "U2") (pin "14") (pinfunction "DRAIN7_14") (pintype "output"))
      (node (ref "U4") (pin "9") (pinfunction "B8_9") (pintype "bidirectional"))
    )
    (net (code "26") (name "GPIB_DAV") (class "Default")
      (node (ref "PL1") (pin "6") (pinfunction "6_6") (pintype "passive"))
      (node (ref "U3") (pin "7") (pinfunction "DAV_2_7") (pintype "bidirectional"))
    )
    (net (code "27") (name "GPIB_EOI") (class "Default")
      (node (ref "PL1") (pin "5") (pinfunction "5_5") (pintype "passive"))
      (node (ref "U3") (pin "8") (pinfunction "EOI_2_8") (pintype "bidirectional"))
    )
    (net (code "28") (name "GPIB_IFC") (class "Default")
      (node (ref "PL1") (pin "9") (pinfunction "9_9") (pintype "passive"))
      (node (ref "U3") (pin "4") (pinfunction "IFC_2_4") (pintype "bidirectional"))
    )
    (net (code "29") (name "GPIB_NDAC") (class "Default")
      (node (ref "PL1") (pin "8") (pinfunction "8_8") (pintype "passive"))
      (node (ref "U3") (pin "5") (pinfunction "NDAC_2_5") (pintype "bidirectional"))
    )
    (net (code "30") (name "GPIB_NRFD") (class "Default")
      (node (ref "PL1") (pin "7") (pinfunction "7_7") (pintype "passive"))
      (node (ref "U3") (pin "6") (pinfunction "NRFD_2_6") (pintype "bidirectional"))
    )
    (net (code "31") (name "GPIB_REN") (class "Default")
      (node (ref "PL1") (pin "17") (pinfunction "17_17") (pintype "passive"))
      (node (ref "U3") (pin "3") (pinfunction "REN_2_3") (pintype "bidirectional"))
    )
    (net (code "32") (name "GPIB_SRQ") (class "Default")
      (node (ref "PL1") (pin "10") (pinfunction "10_10") (pintype "passive"))
      (node (ref "U3") (pin "10") (pinfunction "SRQ_2_10") (pintype "bidirectional"))
    )
    (net (code "33") (name "HC595_RCLK") (class "Default")
      (node (ref "U1") (pin "42") (pinfunction "PB2(AIN0/INT2)_42") (pintype "bidirectional"))
      (node (ref "U2") (pin "9") (pinfunction "RCK_9") (pintype "input"))
    )
    (net (code "34") (name "I2C_VDDIO") (class "Default")
      (node (ref "C18") (pin "1") (pinfunction "1_1") (pintype "passive"))
      (node (ref "J10") (pin "2") (pinfunction "2_2") (pintype "power_in"))
      (node (ref "Q1") (pin "2") (pinfunction "G1_2") (pintype "bidirectional"))
      (node (ref "Q1") (pin "5") (pinfunction "G2_5") (pintype "bidirectional"))
      (node (ref "R14") (pin "1") (pinfunction "1_1") (pintype "passive"))
      (node (ref "R15") (pin "1") (pinfunction "1_1") (pintype "passive"))
      (node (ref "R30") (pin "2") (pinfunction "2_2") (pintype "passive"))
      (node (ref "R31") (pin "2") (pinfunction "2_2") (pintype "passive"))
    )
    (net (code "35") (name "MISO") (class "Default")
      (node (ref "J2") (pin "1") (pinfunction "1_1") (pintype "bidirectional"))
      (node (ref "R55") (pin "2") (pinfunction "2_2") (pintype "passive"))
      (node (ref "U1") (pin "2") (pinfunction "PB6(0C3A/MISO)_2") (pintype "bidirectional"))
    )
    (net (code "36") (name "MISO_5V") (class "Default")
      (node (ref "R55") (pin "1") (pinfunction "1_1") (pintype "passive"))
      (node (ref "U8") (pin "13") (pinfunction "B1_13") (pintype "bidirectional"))
    )
    (net (code "37") (name "MOSI") (class "Default")
      (node (ref "J2") (pin "4") (pinfunction "4_4") (pintype "bidirectional"))
      (node (ref "R57") (pin "2") (pinfunction "2_2") (pintype "passive"))
      (node (ref "U1") (pin "1") (pinfunction "PB5(ICP3/MOSI)_1") (pintype "bidirectional"))
      (node (ref "U2") (pin "22") (pinfunction "SERIN_22") (pintype "input"))
    )
    (net (code "38") (name "MOSI_5V0") (class "Default")
      (node (ref "R57") (pin "1") (pinfunction "1_1") (pintype "passive"))
      (node (ref "U8") (pin "11") (pinfunction "B3_11") (pintype "bidirectional"))
    )
    (net (code "39") (name "NRESET") (class "Default")
      (node (ref "J2") (pin "5") (pinfunction "5_5") (pintype "bidirectional"))
      (node (ref "R7") (pin "1") (pinfunction "1_1") (pintype "passive"))
      (node (ref "U1") (pin "4") (pinfunction "~{RESET}_4") (pintype "bidirectional"))
    )
    (net (code "40") (name "Net-(C11-Pad1)") (class "Default")
      (node (ref "C11") (pin "1") (pinfunction "1_1") (pintype "passive"))
      (node (ref "F2") (pin "1") (pinfunction "1_1") (pintype "bidirectional"))
      (node (ref "J4") (pin "VBUS") (pinfunction "VBUS_VBUS") (pintype "power_in"))
    )
    (net (code "41") (name "Net-(J1-PWR)") (class "Default")
      (node (ref "D2") (pin "A") (pinfunction "A_A") (pintype "passive"))
      (node (ref "J1") (pin "VIN0") (pinfunction "PWR_VIN0") (pintype "bidirectional"))
    )
    (net (code "42") (name "Net-(LED1-PadA)") (class "Default")
      (node (ref "LED1") (pin "A") (pinfunction "A_A") (pintype "passive"))
      (node (ref "R2") (pin "2") (pinfunction "2_2") (pintype "passive"))
    )
    (net (code "43") (name "Net-(LED2-PadA)") (class "Default")
      (node (ref "LED2") (pin "A") (pinfunction "A_A") (pintype "passive"))
      (node (ref "R53") (pin "2") (pinfunction "2_2") (pintype "passive"))
    )
    (net (code "44") (name "Net-(LED3-PadA)") (class "Default")
      (node (ref "LED3") (pin "A") (pinfunction "A_A") (pintype "passive"))
      (node (ref "R23") (pin "1") (pinfunction "1_1") (pintype "passive"))
    )
    (net (code "45") (name "Net-(LED4-PadA)") (class "Default")
      (node (ref "LED4") (pin "A") (pinfunction "A_A") (pintype "passive"))
      (node (ref "R24") (pin "1") (pinfunction "1_1") (pintype "passive"))
    )
    (net (code "46") (name "Net-(LED5-PadA)") (class "Default")
      (node (ref "LED5") (pin "A") (pinfunction "A_A") (pintype "passive"))
      (node (ref "R6") (pin "2") (pinfunction "2_2") (pintype "passive"))
    )
    (net (code "47") (name "Net-(LED6-PadA)") (class "Default")
      (node (ref "LED6") (pin "A") (pinfunction "A_A") (pintype "passive"))
      (node (ref "R52") (pin "2") (pinfunction "2_2") (pintype "passive"))
    )
    (net (code "48") (name "Net-(U1-PC6(TOSC1))") (class "Default")
      (node (ref "R2") (pin "1") (pinfunction "1_1") (pintype "passive"))
      (node (ref "U1") (pin "25") (pinfunction "PC6(TOSC1)_25") (pintype "bidirectional"))
    )
    (net (code "49") (name "Net-(U1-PC7(TOSC2))") (class "Default")
      (node (ref "R53") (pin "1") (pinfunction "1_1") (pintype "passive"))
      (node (ref "U1") (pin "26") (pinfunction "PC7(TOSC2)_26") (pintype "bidirectional"))
    )
    (net (code "50") (name "Net-(U1-XTAL1)") (class "Default")
      (node (ref "C4") (pin "2") (pinfunction "2_2") (pintype "passive"))
      (node (ref "U1") (pin "8") (pinfunction "XTAL1_8") (pintype "bidirectional"))
      (node (ref "Y2") (pin "3") (pinfunction "2_3") (pintype "passive"))
    )
    (net (code "51") (name "Net-(U1-XTAL2)") (class "Default")
      (node (ref "C3") (pin "2") (pinfunction "2_2") (pintype "passive"))
      (node (ref "U1") (pin "7") (pinfunction "XTAL2_7") (pintype "bidirectional"))
      (node (ref "Y2") (pin "1") (pinfunction "1_1") (pintype "passive"))
    )
    (net (code "52") (name "Net-(U2-~{G})") (class "Default")
      (node (ref "U2") (pin "4") (pinfunction "~{G}_4") (pintype "input"))
      (node (ref "U6") (pin "4") (pinfunction "Y_4") (pintype "bidirectional"))
    )
    (net (code "53") (name "Net-(U9-ADJ)") (class "Default")
      (node (ref "R1") (pin "2") (pinfunction "2_2") (pintype "passive"))
      (node (ref "R49") (pin "1") (pinfunction "1_1") (pintype "passive"))
      (node (ref "U9") (pin "1") (pinfunction "ADJ_1") (pintype "input"))
    )
    (net (code "54") (name "Net-(U11-~{MR})") (class "Default")
      (node (ref "S1") (pin "3") (pinfunction "3_3") (pintype "passive"))
      (node (ref "S1") (pin "4") (pinfunction "4_4") (pintype "passive"))
      (node (ref "U11") (pin "3") (pinfunction "~{MR}_3") (pintype "input"))
    )
    (net (code "55") (name "Net-(U11-~{RESET})") (class "Default")
      (node (ref "R3") (pin "1") (pinfunction "1_1") (pintype "passive"))
      (node (ref "R7") (pin "2") (pinfunction "2_2") (pintype "passive"))
      (node (ref "U11") (pin "2") (pinfunction "~{RESET}_2") (pintype "output"))
    )
    (net (code "56") (name "PA0") (class "Default")
      (node (ref "R8") (pin "2") (pinfunction "2_2") (pintype "passive"))
      (node (ref "U1") (pin "37") (pinfunction "PA0(ADC0/PCINT0)_37") (pintype "bidirectional"))
    )
    (net (code "57") (name "PA0_D1") (class "Default")
      (node (ref "R8") (pin "1") (pinfunction "1_1") (pintype "passive"))
      (node (ref "U4") (pin "19") (pinfunction "D1_19") (pintype "bidirectional"))
    )
    (net (code "58") (name "PA1") (class "Default")
      (node (ref "R9") (pin "2") (pinfunction "2_2") (pintype "passive"))
      (node (ref "U1") (pin "36") (pinfunction "PA1(ADC1/PCINT1)_36") (pintype "bidirectional"))
    )
    (net (code "59") (name "PA1_D2") (class "Default")
      (node (ref "R9") (pin "1") (pinfunction "1_1") (pintype "passive"))
      (node (ref "U4") (pin "18") (pinfunction "D2_18") (pintype "bidirectional"))
    )
    (net (code "60") (name "PA2") (class "Default")
      (node (ref "R10") (pin "2") (pinfunction "2_2") (pintype "passive"))
      (node (ref "U1") (pin "35") (pinfunction "PA2(ADC2/PCINT2)_35") (pintype "bidirectional"))
    )
    (net (code "61") (name "PA2_D3") (class "Default")
      (node (ref "R10") (pin "1") (pinfunction "1_1") (pintype "passive"))
      (node (ref "U4") (pin "17") (pinfunction "D3_17") (pintype "bidirectional"))
    )
    (net (code "62") (name "PA3") (class "Default")
      (node (ref "R11") (pin "2") (pinfunction "2_2") (pintype "passive"))
      (node (ref "U1") (pin "34") (pinfunction "PA3(ADC3/PCINT3)_34") (pintype "bidirectional"))
    )
    (net (code "63") (name "PA3_D4") (class "Default")
      (node (ref "R11") (pin "1") (pinfunction "1_1") (pintype "passive"))
      (node (ref "U4") (pin "16") (pinfunction "D4_16") (pintype "bidirectional"))
    )
    (net (code "64") (name "PA4") (class "Default")
      (node (ref "R13") (pin "2") (pinfunction "2_2") (pintype "passive"))
      (node (ref "U1") (pin "33") (pinfunction "PA4(ADC4/PCINT4)_33") (pintype "bidirectional"))
    )
    (net (code "65") (name "PA4_D5") (class "Default")
      (node (ref "R13") (pin "1") (pinfunction "1_1") (pintype "passive"))
      (node (ref "U4") (pin "15") (pinfunction "D5_15") (pintype "bidirectional"))
    )
    (net (code "66") (name "PA5") (class "Default")
      (node (ref "R25") (pin "2") (pinfunction "2_2") (pintype "passive"))
      (node (ref "U1") (pin "32") (pinfunction "PA5(ADC5/PCINT5)_32") (pintype "bidirectional"))
    )
    (net (code "67") (name "PA5_D6") (class "Default")
      (node (ref "R25") (pin "1") (pinfunction "1_1") (pintype "passive"))
      (node (ref "U4") (pin "14") (pinfunction "D6_14") (pintype "bidirectional"))
    )
    (net (code "68") (name "PA6") (class "Default")
      (node (ref "R26") (pin "2") (pinfunction "2_2") (pintype "passive"))
      (node (ref "U1") (pin "31") (pinfunction "PA6(ADC6/PCINT6)_31") (pintype "bidirectional"))
    )
    (net (code "69") (name "PA6_D7") (class "Default")
      (node (ref "R26") (pin "1") (pinfunction "1_1") (pintype "passive"))
      (node (ref "U4") (pin "13") (pinfunction "D7_13") (pintype "bidirectional"))
    )
    (net (code "70") (name "PA7") (class "Default")
      (node (ref "R27") (pin "2") (pinfunction "2_2") (pintype "passive"))
      (node (ref "U1") (pin "30") (pinfunction "PA7(ADC7/PCINT7)_30") (pintype "bidirectional"))
    )
    (net (code "71") (name "PA7_D8") (class "Default")
      (node (ref "R27") (pin "1") (pinfunction "1_1") (pintype "passive"))
      (node (ref "U4") (pin "12") (pinfunction "D8_12") (pintype "bidirectional"))
    )
    (net (code "72") (name "PB0_EOI") (class "Default")
      (node (ref "U1") (pin "40") (pinfunction "PB0(XCKO/T0/PCINT8)_40") (pintype "bidirectional"))
      (node (ref "U3") (pin "17") (pinfunction "EOI_17") (pintype "bidirectional"))
      (node (ref "U6") (pin "1") (pinfunction "A_1") (pintype "bidirectional"))
    )
    (net (code "73") (name "PB1_DAV") (class "Default")
      (node (ref "U1") (pin "41") (pinfunction "PB1(T1/CLK0/PCINT9)_41") (pintype "bidirectional"))
      (node (ref "U3") (pin "18") (pinfunction "DAV_18") (pintype "bidirectional"))
    )
    (net (code "74") (name "PB3_CS") (class "Default")
      (node (ref "R58") (pin "2") (pinfunction "2_2") (pintype "passive"))
      (node (ref "U1") (pin "43") (pinfunction "PB3(AIN1/OC0A)_43") (pintype "bidirectional"))
      (node (ref "U8") (pin "10") (pinfunction "B4_10") (pintype "bidirectional"))
    )
    (net (code "75") (name "PB4_CD") (class "Default")
      (node (ref "R54") (pin "2") (pinfunction "2_2") (pintype "passive"))
      (node (ref "U1") (pin "44") (pinfunction "PB4(SS/OC0B)_44") (pintype "bidirectional"))
    )
    (net (code "76") (name "PD2_NRFD") (class "Default")
      (node (ref "U1") (pin "11") (pinfunction "PD2(RXD1/INT0)_11") (pintype "bidirectional"))
      (node (ref "U3") (pin "19") (pinfunction "NRFD_19") (pintype "bidirectional"))
    )
    (net (code "77") (name "PD3_NDAC") (class "Default")
      (node (ref "U1") (pin "12") (pinfunction "PD3(TXD1/INT1)_12") (pintype "bidirectional"))
      (node (ref "U3") (pin "20") (pinfunction "NDAC_20") (pintype "bidirectional"))
    )
    (net (code "78") (name "PD4_IFC") (class "Default")
      (node (ref "U1") (pin "13") (pinfunction "PD4(XCK1/OC1B)_13") (pintype "bidirectional"))
      (node (ref "U2") (pin "3") (pinfunction "~{SRCLR}_3") (pintype "input"))
      (node (ref "U3") (pin "21") (pinfunction "IFC_21") (pintype "bidirectional"))
    )
    (net (code "79") (name "PD5_SRQ") (class "Default")
      (node (ref "U1") (pin "14") (pinfunction "PD5(OC1A)_14") (pintype "bidirectional"))
      (node (ref "U3") (pin "15") (pinfunction "SRQ_15") (pintype "bidirectional"))
    )
    (net (code "80") (name "PD6_ATN") (class "Default")
      (node (ref "U1") (pin "15") (pinfunction "PD6(OC2B/ICP)_15") (pintype "bidirectional"))
      (node (ref "U3") (pin "16") (pinfunction "ATN_16") (pintype "bidirectional"))
      (node (ref "U6") (pin "2") (pinfunction "B_2") (pintype "bidirectional"))
    )
    (net (code "81") (name "PD7_REN") (class "Default")
      (node (ref "U1") (pin "16") (pinfunction "PD7(OC2A)_16") (pintype "bidirectional"))
      (node (ref "U3") (pin "22") (pinfunction "REN_22") (pintype "bidirectional"))
    )
    (net (code "82") (name "PE") (class "Default")
      (node (ref "J9") (pin "3") (pinfunction "3_3") (pintype "passive"))
      (node (ref "U1") (pin "22") (pinfunction "PC3(TMS)_22") (pintype "bidirectional"))
      (node (ref "U4") (pin "11") (pinfunction "PE_11") (pintype "input"))
    )
    (net (code "83") (name "RXD") (class "Default")
      (node (ref "R19") (pin "1") (pinfunction "1_1") (pintype "passive"))
      (node (ref "U1") (pin "9") (pinfunction "PD0(RXD0/T3*)_9") (pintype "bidirectional"))
    )
    (net (code "84") (name "RXLED") (class "Default")
      (node (ref "LED5") (pin "C") (pinfunction "C_C") (pintype "passive"))
      (node (ref "U7") (pin "22") (pinfunction "RXLED_22") (pintype "input"))
    )
    (net (code "85") (name "SC") (class "Default")
      (node (ref "J9") (pin "1") (pinfunction "1_1") (pintype "passive"))
      (node (ref "U1") (pin "24") (pinfunction "PC5(TDI)_24") (pintype "bidirectional"))
      (node (ref "U3") (pin "1") (pinfunction "SC_1") (pintype "input"))
    )
    (net (code "86") (name "SCK") (class "Default")
      (node (ref "J2") (pin "3") (pinfunction "3_3") (pintype "bidirectional"))
      (node (ref "R56") (pin "2") (pinfunction "2_2") (pintype "passive"))
      (node (ref "U1") (pin "3") (pinfunction "PB7(OC3B/SCK)_3") (pintype "bidirectional"))
      (node (ref "U2") (pin "10") (pinfunction "SRCK_10") (pintype "input"))
    )
    (net (code "87") (name "SCL") (class "Default")
      (node (ref "J10") (pin "4") (pinfunction "4_4") (pintype "passive"))
      (node (ref "Q1") (pin "1") (pinfunction "S1_1") (pintype "bidirectional"))
      (node (ref "R14") (pin "2") (pinfunction "2_2") (pintype "passive"))
    )
    (net (code "88") (name "SDA") (class "Default")
      (node (ref "J10") (pin "3") (pinfunction "3_3") (pintype "passive"))
      (node (ref "Q1") (pin "4") (pinfunction "S2_4") (pintype "bidirectional"))
      (node (ref "R15") (pin "2") (pinfunction "2_2") (pintype "passive"))
    )
    (net (code "89") (name "SD_CD") (class "Default")
      (node (ref "J3") (pin "CD") (pinfunction "CD_CD") (pintype "bidirectional"))
      (node (ref "R12") (pin "1") (pinfunction "1_1") (pintype "passive"))
      (node (ref "R54") (pin "1") (pinfunction "1_1") (pintype "passive"))
    )
    (net (code "90") (name "SD_CLK") (class "Default")
      (node (ref "J3") (pin "5") (pinfunction "CLK_5") (pintype "bidirectional"))
      (node (ref "U8") (pin "3") (pinfunction "A2_3") (pintype "bidirectional"))
    )
    (net (code "91") (name "SD_CS") (class "Default")
      (node (ref "J3") (pin "1") (pinfunction "CD/DAT3_1") (pintype "bidirectional"))
      (node (ref "U8") (pin "5") (pinfunction "A4_5") (pintype "bidirectional"))
    )
    (net (code "92") (name "SD_DAT1") (class "Default")
      (node (ref "J3") (pin "8") (pinfunction "DAT1_8") (pintype "bidirectional"))
      (node (ref "R16") (pin "1") (pinfunction "1_1") (pintype "passive"))
    )
    (net (code "93") (name "SD_DAT2") (class "Default")
      (node (ref "J3") (pin "9") (pinfunction "DAT2_9") (pintype "bidirectional"))
      (node (ref "R17") (pin "1") (pinfunction "1_1") (pintype "passive"))
    )
    (net (code "94") (name "SD_MISO") (class "Default")
      (node (ref "J3") (pin "7") (pinfunction "DAT0_7") (pintype "bidirectional"))
      (node (ref "R18") (pin "1") (pinfunction "1_1") (pintype "passive"))
      (node (ref "U8") (pin "2") (pinfunction "A1_2") (pintype "bidirectional"))
    )
    (net (code "95") (name "SD_MOSI") (class "Default")
      (node (ref "J3") (pin "2") (pinfunction "CMD_2") (pintype "bidirectional"))
      (node (ref "U8") (pin "4") (pinfunction "A3_4") (pintype "bidirectional"))
    )
    (net (code "96") (name "SD_WP") (class "Default")
      (node (ref "J3") (pin "WP") (pinfunction "WP_WP") (pintype "bidirectional"))
      (node (ref "R59") (pin "2") (pinfunction "2_2") (pintype "passive"))
      (node (ref "R60") (pin "1") (pinfunction "1_1") (pintype "passive"))
    )
    (net (code "97") (name "TE") (class "Default")
      (node (ref "J9") (pin "4") (pinfunction "4_4") (pintype "passive"))
      (node (ref "R5") (pin "1") (pinfunction "1_1") (pintype "passive"))
      (node (ref "U1") (pin "21") (pinfunction "PC2(TCK)_21") (pintype "bidirectional"))
      (node (ref "U3") (pin "2") (pinfunction "TE_2") (pintype "input"))
      (node (ref "U4") (pin "1") (pinfunction "TE_1") (pintype "input"))
    )
    (net (code "98") (name "TXD") (class "Default")
      (node (ref "R20") (pin "1") (pinfunction "1_1") (pintype "passive"))
      (node (ref "U1") (pin "10") (pinfunction "PD1(TXD0)_10") (pintype "bidirectional"))
    )
    (net (code "99") (name "TXLED") (class "Default")
      (node (ref "LED6") (pin "C") (pinfunction "C_C") (pintype "passive"))
      (node (ref "U7") (pin "23") (pinfunction "TXLED_23") (pintype "input"))
    )
    (net (code "100") (name "USBVCC") (class "Default")
      (node (ref "C16") (pin "1") (pinfunction "1_1") (pintype "passive"))
      (node (ref "C17") (pin "+") (pinfunction "+_+") (pintype "passive"))
      (node (ref "F2") (pin "2") (pinfunction "2_2") (pintype "bidirectional"))
      (node (ref "U7") (pin "20") (pinfunction "VCC_20") (pintype "power_in"))
    )
    (net (code "101") (name "VIN") (class "Default")
      (node (ref "C14") (pin "+") (pinfunction "+_+") (pintype "passive"))
      (node (ref "D2") (pin "C") (pinfunction "C_C") (pintype "passive"))
      (node (ref "J5") (pin "1") (pinfunction "1_1") (pintype "passive"))
      (node (ref "U9") (pin "3") (pinfunction "IN_3") (pintype "input"))
    )
    (net (code "102") (name "unconnected-(J4-PadID)") (class "Default")
      (node (ref "J4") (pin "ID") (pinfunction "ID_ID") (pintype "bidirectional"))
    )
    (net (code "103") (name "unconnected-(U2-SEROUT-Pad15)") (class "Default")
      (node (ref "U2") (pin "15") (pinfunction "SEROUT_15") (pintype "output"))
    )
    (net (code "104") (name "unconnected-(U3-NC-Pad23)") (class "Default")
      (node (ref "U3") (pin "23") (pinfunction "NC_23") (pintype "passive"))
    )
    (net (code "105") (name "unconnected-(U3-NC_2-Pad11)") (class "Default")
      (node (ref "U3") (pin "11") (pinfunction "NC_2_11") (pintype "passive"))
    )
    (net (code "106") (name "unconnected-(U3-NC_3-Pad14)") (class "Default")
      (node (ref "U3") (pin "14") (pinfunction "NC_3_14") (pintype "passive"))
    )
    (net (code "107") (name "unconnected-(U7-CTS-Pad11)") (class "Default")
      (node (ref "U7") (pin "11") (pinfunction "CTS_11") (pintype "input"))
    )
    (net (code "108") (name "unconnected-(U7-DCD-Pad10)") (class "Default")
      (node (ref "U7") (pin "10") (pinfunction "DCD_10") (pintype "input"))
    )
    (net (code "109") (name "unconnected-(U7-DSR-Pad9)") (class "Default")
      (node (ref "U7") (pin "9") (pinfunction "DSR_9") (pintype "input"))
    )
    (net (code "110") (name "unconnected-(U7-DTR-Pad2)") (class "Default")
      (node (ref "U7") (pin "2") (pinfunction "DTR_2") (pintype "output"))
    )
    (net (code "111") (name "unconnected-(U7-OSCI-Pad27)") (class "Default")
      (node (ref "U7") (pin "27") (pinfunction "OSCI_27") (pintype "input"))
    )
    (net (code "112") (name "unconnected-(U7-OSCO-Pad28)") (class "Default")
      (node (ref "U7") (pin "28") (pinfunction "OSCO_28") (pintype "output"))
    )
    (net (code "113") (name "unconnected-(U7-PWREN-Pad14)") (class "Default")
      (node (ref "U7") (pin "14") (pinfunction "PWREN_14") (pintype "input"))
    )
    (net (code "114") (name "unconnected-(U7-RESET-Pad19)") (class "Default")
      (node (ref "U7") (pin "19") (pinfunction "RESET_19") (pintype "input"))
    )
    (net (code "115") (name "unconnected-(U7-RI-Pad6)") (class "Default")
      (node (ref "U7") (pin "6") (pinfunction "RI_6") (pintype "input"))
    )
    (net (code "116") (name "unconnected-(U7-RTS-Pad3)") (class "Default")
      (node (ref "U7") (pin "3") (pinfunction "RTS_3") (pintype "output"))
    )
    (net (code "117") (name "unconnected-(U7-SLEEP-Pad12)") (class "Default")
      (node (ref "U7") (pin "12") (pinfunction "SLEEP_12") (pintype "input"))
    )
    (net (code "118") (name "unconnected-(U7-TXDEN-Pad13)") (class "Default")
      (node (ref "U7") (pin "13") (pinfunction "TXDEN_13") (pintype "input"))
    )
    (net (code "119") (name "unconnected-(U10-BP-Pad4)") (class "Default")
      (node (ref "U10") (pin "4") (pinfunction "BP_4") (pintype "input"))
    )
  )
)
